# 1_PowerSupply.net
KiCad netlist of a schematic drawn in Altium Designer
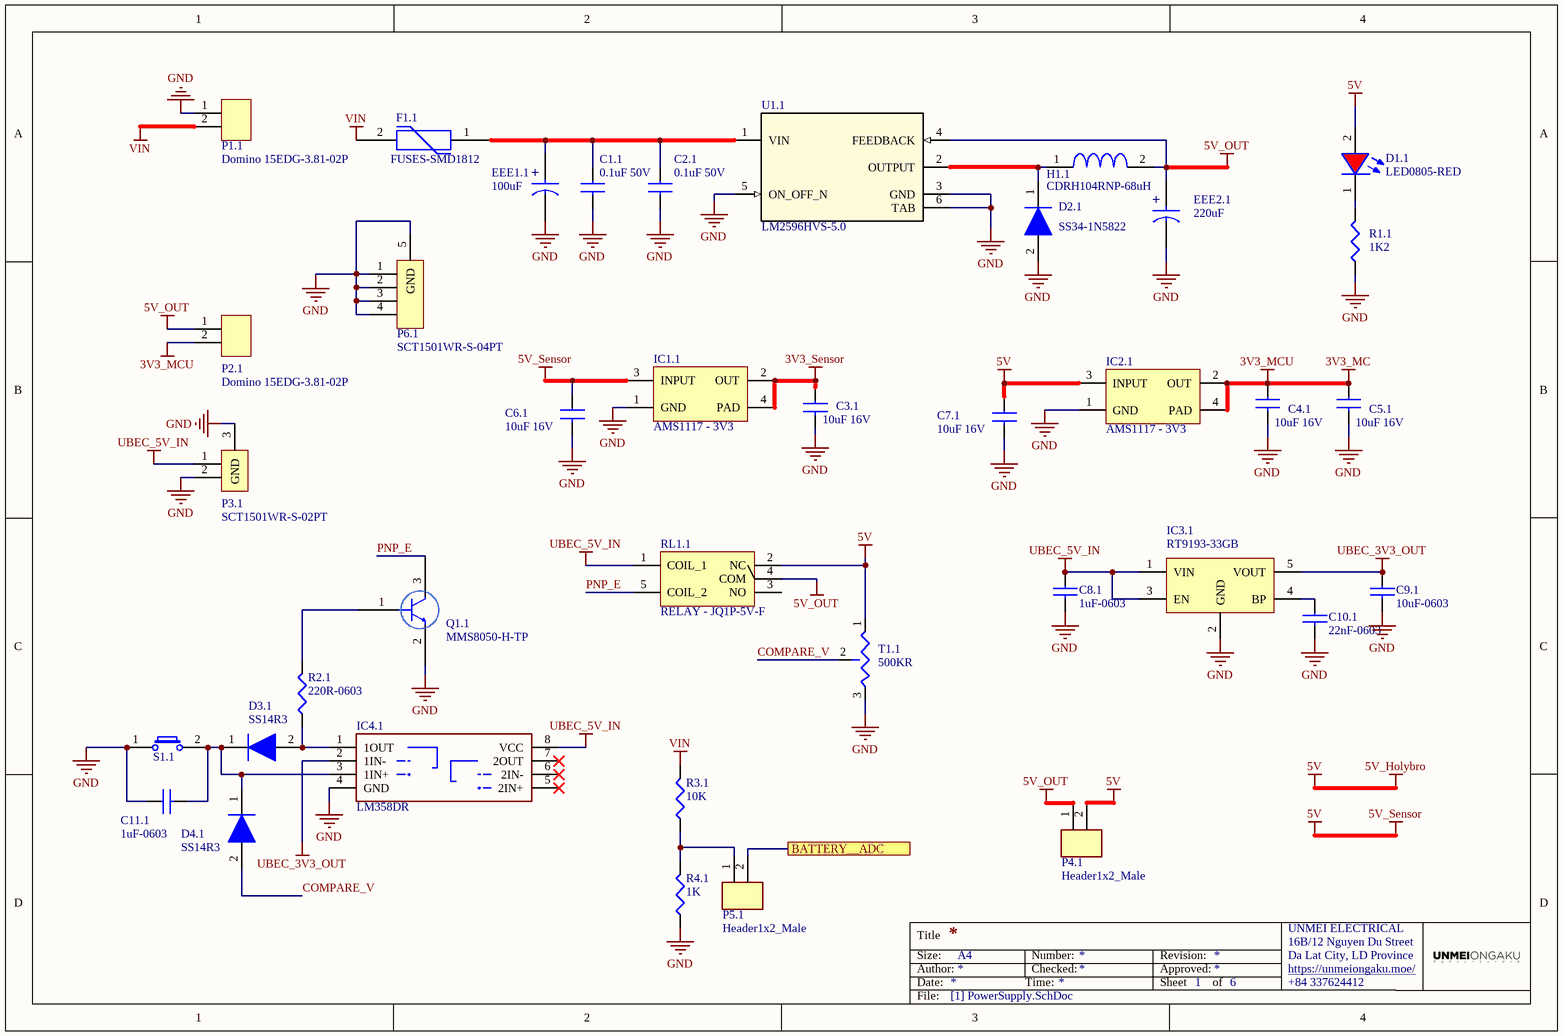
[diagram p0: [1] PowerSupply.SchDoc]

(export (version "E")
  (design (tool "Eeschema 10.0.6"))
  (components
    (comp (ref "C1.1")
      (value "0.1uF 50V")
      (footprint "CAP0805")
      (description "Cap Ceramic 0.1uF 50V X7R 10% SMD 2.0 x 1.2 mm 125 C Paper T/R")
      (fields
        (field (name "MANUFACTURER") "KEMET")
        (field (name "MANUFACTURER PART NUMBER") "C0805C104K5RACTU")
      )
      (libsource (lib "Minh_Lib") (part "C0805C104K5RACTU"))
    )
    (comp (ref "C2.1")
      (value "0.1uF 50V")
      (footprint "CAP0805")
      (description "Cap Ceramic 0.1uF 50V X7R 10% SMD 2.0 x 1.2 mm 125 C Paper T/R")
      (fields
        (field (name "MANUFACTURER") "KEMET")
        (field (name "MANUFACTURER PART NUMBER") "C0805C104K5RACTU")
      )
      (libsource (lib "Minh_Lib") (part "C0805C104K5RACTU"))
    )
    (comp (ref "C3.1")
      (value "10uF 16V")
      (footprint "CAP0805")
      (description "Ceramic Capacitors MLCC - SMD/SMT 16V 10uF X5R 0805 10%")
      (fields
        (field (name "MANUFACTURER") "KEMET")
        (field (name "MANUFACTURER PART NUMBER") "C0805C106K4PACTU")
      )
      (libsource (lib "Minh_Lib") (part "C0805C106K4PACTU"))
    )
    (comp (ref "C4.1")
      (value "10uF 16V")
      (footprint "CAP0805")
      (description "Ceramic Capacitors MLCC - SMD/SMT 16V 10uF X5R 0805 10%")
      (fields
        (field (name "MANUFACTURER") "KEMET")
        (field (name "MANUFACTURER PART NUMBER") "C0805C106K4PACTU")
      )
      (libsource (lib "Minh_Lib") (part "C0805C106K4PACTU"))
    )
    (comp (ref "C5.1")
      (value "10uF 16V")
      (footprint "CAP0805")
      (description "Ceramic Capacitors MLCC - SMD/SMT 16V 10uF X5R 0805 10%")
      (fields
        (field (name "MANUFACTURER") "KEMET")
        (field (name "MANUFACTURER PART NUMBER") "C0805C106K4PACTU")
      )
      (libsource (lib "Minh_Lib") (part "C0805C106K4PACTU"))
    )
    (comp (ref "C6.1")
      (value "10uF 16V")
      (footprint "CAP0805")
      (description "Ceramic Capacitors MLCC - SMD/SMT 16V 10uF X5R 0805 10%")
      (fields
        (field (name "MANUFACTURER") "KEMET")
        (field (name "MANUFACTURER PART NUMBER") "C0805C106K4PACTU")
      )
      (libsource (lib "Minh_Lib") (part "C0805C106K4PACTU"))
    )
    (comp (ref "C7.1")
      (value "10uF 16V")
      (footprint "CAP0805")
      (description "Ceramic Capacitors MLCC - SMD/SMT 16V 10uF X5R 0805 10%")
      (fields
        (field (name "MANUFACTURER") "KEMET")
        (field (name "MANUFACTURER PART NUMBER") "C0805C106K4PACTU")
      )
      (libsource (lib "Minh_Lib") (part "C0805C106K4PACTU"))
    )
    (comp (ref "C8.1")
      (value "1uF-0603")
      (footprint "CAP0603")
      (description "CAP CER 1UF 16V X7R 0603")
      (fields (field (name "TOLERANCE") "±10%"))
      (libsource (lib "Minh_Lib") (part "CC0603KRX7R7BB105"))
    )
    (comp (ref "C9.1")
      (value "10uF-0603")
      (footprint "CAP0603")
      (description "CAP CER 10UF 10V X5R 0603")
      (fields (field (name "TOLERANCE") "±10%"))
      (libsource (lib "Minh_Lib") (part "CC0603KRX5R6BB106"))
    )
    (comp (ref "C10.1")
      (value "22nF-0603")
      (footprint "CAP0603")
      (description "Multilayer Ceramic Capacitors MLCC - SMD/SMT 22nF 50V X7R 10%")
      (fields
        (field (name "MANUFACTURER") "Yageo")
        (field (name "MANUFACTURER PART NUMBER") "CC0603KRX7R9BB223")
      )
      (libsource (lib "Minh_Lib") (part "CC0603KRX7R9BB223"))
    )
    (comp (ref "C11.1")
      (value "1uF-0603")
      (footprint "CAP0603")
      (description "CAP CER 1UF 16V X7R 0603")
      (fields (field (name "TOLERANCE") "±10%"))
      (libsource (lib "Minh_Lib") (part "CC0603KRX7R7BB105"))
    )
    (comp (ref "D1.1")
      (value "LED0805-RED")
      (footprint "LED0805-RED")
      (libsource (lib "Minh_Lib") (part "LED0805-RED"))
    )
    (comp (ref "D2.1")
      (value "SS34-1N5822")
      (footprint "SS34 - 1N5822 / DO-214AA, SMA")
      (description "SS Series 500 mV 3 A 40 V Max Reverse Voltage Schottky Rectifier - DO-214AB")
      (fields
        (field (name "MANUFACTURER") "ON Semiconductor / Fairchild")
        (field (name "MANUFACTURER PART NUMBER") "SS34")
      )
      (libsource (lib "Minh_Lib") (part "SS34"))
    )
    (comp (ref "D3.1")
      (value "SS14R3")
      (footprint "SS14 - 1N5819 / DO-214AA, SMA")
      (description "1A, 40V, Schottky Rectifier")
      (fields (field (name "MANUFACTURER") "Taiwan Semiconductor"))
      (libsource (lib "Minh_Lib") (part "SS14R3"))
    )
    (comp (ref "D4.1")
      (value "SS14R3")
      (footprint "SS14 - 1N5819 / DO-214AA, SMA")
      (description "1A, 40V, Schottky Rectifier")
      (fields (field (name "MANUFACTURER") "Taiwan Semiconductor"))
      (libsource (lib "Minh_Lib") (part "SS14R3"))
    )
    (comp (ref "EEE1.1")
      (value "100uF")
      (footprint "CAPACITOR/ALU - SIZE D8/SMD - 6.3X7.7")
      (description "Cap Aluminum 100uF 25V 20% (6.3 X 7.7mm) SMD 143mA 2000h 85°C T/R")
      (fields
        (field (name "MANUFACTURER") "Panasonic")
        (field (name "MANUFACTURER PART NUMBER") "EEE-1EA101XP")
      )
      (libsource (lib "Minh_Lib") (part "EEE-1EA101XP"))
    )
    (comp (ref "EEE2.1")
      (value "220uF")
      (footprint "CAPACITOR/ALU - SIZE D8/SMD - 6.3X7.7")
      (description "Cap Aluminum 100uF 25V 20% (6.3 X 7.7mm) SMD 143mA 2000h 85°C T/R")
      (fields
        (field (name "MANUFACTURER") "Panasonic")
        (field (name "MANUFACTURER PART NUMBER") "EEE-1EA101XP")
      )
      (libsource (lib "Minh_Lib") (part "EEE-1EA101XP"))
    )
    (comp (ref "F1.1")
      (value "FUSES-SMD1812")
      (footprint "FUSES - SMD1812")
      (libsource (lib "Minh_Lib") (part "FUSES-SMD1812"))
    )
    (comp (ref "H1.1")
      (value "CDRH104RNP-68uH")
      (footprint "CDRH104RNP")
      (description "Ind Power Shielded Wirewound 68uH 30% 100KHz Ferrite 1.42A Carrier T/R")
      (fields
        (field (name "MANUFACTURER") "Sumida")
        (field (name "MANUFACTURER PART NUMBER") "CDRH104RNP-680NC")
      )
      (libsource (lib "Minh_Lib") (part "CDRH104RNP-680NC"))
    )
    (comp (ref "IC1.1")
      (value "AMS1117 - 3V3")
      (footprint "SOT223-4M_AMS1117_3V3")
      (description "LDO Voltage Regulators 3.3V 1A Positive")
      (fields
        (field (name "MANUFACTURER") "ON Semiconductor")
        (field (name "MANUFACTURER PART NUMBER") "NCP1117ST33T3G")
      )
      (libsource (lib "Minh_Lib") (part "AMS1117 - 3V3"))
    )
    (comp (ref "IC2.1")
      (value "AMS1117 - 3V3")
      (footprint "SOT223-4M_AMS1117_3V3")
      (description "LDO Voltage Regulators 3.3V 1A Positive")
      (fields
        (field (name "MANUFACTURER") "ON Semiconductor")
        (field (name "MANUFACTURER PART NUMBER") "NCP1117ST33T3G")
      )
      (libsource (lib "Minh_Lib") (part "AMS1117 - 3V3"))
    )
    (comp (ref "IC3.1")
      (value "RT9193-33GB")
      (footprint "SOT23-5")
      (description "IC REG LDO 3.3V 0.3A SOT23-5")
      (libsource (lib "Minh_Lib") (part "RT9193-33GB"))
    )
    (comp (ref "IC4.1")
      (value "LM358DR")
      (footprint "SOP8")
      (description "IC OPAMP GP 700KHZ 8SOIC")
      (fields (field (name "MANUFACTURER") "Texas Instruments"))
      (libsource (lib "Minh_Lib") (part "LM358DR"))
    )
    (comp (ref "P1.1")
      (value "Domino 15EDG-3.81-02P")
      (footprint "Domino 15EDG3.81 2P")
      (libsource (lib "Minh_Lib") (part "Domino 15EDG-3.81-02P"))
    )
    (comp (ref "P2.1")
      (value "Domino 15EDG-3.81-02P")
      (footprint "Domino 15EDG3.81 2P")
      (libsource (lib "Minh_Lib") (part "Domino 15EDG-3.81-02P"))
    )
    (comp (ref "P3.1")
      (value "SCT1501WR-S-02PT")
      (footprint "Connector ZH1.5 2P SMD")
      (libsource (lib "Minh_Lib") (part "SCT1501WR-S-02PT"))
    )
    (comp (ref "P4.1")
      (value "Header1x2_Male")
      (footprint "Minh_Lib:HDR1x2_2.54_MALE")
      (description "Header1x2_2.54_MALE")
      (libsource (lib "Minh_Lib") (part "HDR1x2_2.54_MALE"))
    )
    (comp (ref "P5.1")
      (value "Header1x2_Male")
      (footprint "Minh_Lib:HDR1x2_2.54_MALE")
      (description "Header1x2_2.54_MALE")
      (libsource (lib "Minh_Lib") (part "HDR1x2_2.54_MALE"))
    )
    (comp (ref "P6.1")
      (value "SCT1501WR-S-04PT")
      (footprint "Connector ZH1.5 4P SMD")
      (libsource (lib "Minh_Lib") (part "SCT1501WR-S-04PT"))
    )
    (comp (ref "Q1.1")
      (value "MMS8050-H-TP")
      (footprint "SOT23")
      (description "Trans Gp Bjt NPN 25V 0.5A 3-PIN SOT-23 T/r")
      (fields (field (name "MANUFACTURER") "MCC"))
      (libsource (lib "Minh_Lib") (part "MMS8050-H-TP"))
    )
    (comp (ref "R1.1")
      (value "1K2")
      (footprint "RES0805")
      (description "贴片电阻 1.5KΩ ±5% 1/8W ±100ppm/℃ 0805")
      (fields
        (field (name "MANUFACTURER") "Yageo")
        (field (name "MANUFACTURER PART NUMBER") "RC0805JR-071K5L")
      )
      (libsource (lib "Minh_Lib") (part "RC0805JR-071K5L"))
    )
    (comp (ref "R2.1")
      (value "220R-0603")
      (footprint "RES0603 - 3D")
      (description "RES SMD 220 OHM 5% 1/10W 0603")
      (fields (field (name "TOLERANCE") "±5%"))
      (libsource (lib "Minh_Lib") (part "RC0603JR-07220RL"))
    )
    (comp (ref "R3.1")
      (value "10K")
      (footprint "RES0805")
      (description "贴片电阻 10KΩ ±5% 1/8W ±100ppm/℃ 0805")
      (fields
        (field (name "MANUFACTURER") "Yageo")
        (field (name "MANUFACTURER PART NUMBER") "RC0805JR-0710KL")
      )
      (libsource (lib "Minh_Lib") (part "RC0805JR-0710KL"))
    )
    (comp (ref "R4.1")
      (value "1K")
      (footprint "RES0805")
      (description "贴片电阻 1KΩ ±5% 1/8W ±100ppm/℃ 0805")
      (fields
        (field (name "MANUFACTURER") "Yageo")
        (field (name "MANUFACTURER PART NUMBER") "RC0805JR-071KL")
      )
      (libsource (lib "Minh_Lib") (part "RC0805JR-071KL"))
    )
    (comp (ref "RL1.1")
      (value "RELAY - JQ1P-5V-F")
      (footprint "RELAY - JQ1P - XV - F 10A SPDT")
      (description "RELAY GEN PURPOSE SPDT 10A 5V")
      (fields (field (name "MANUFACTURER") "Panasonic") (field (name "MANUFACTURER PART NUMBER") "JQ1P-5V-F"))
      (libsource (lib "Minh_Lib") (part "RELAY - JQ1P-5V-F"))
    )
    (comp (ref "S1.1")
      (value "434121043816")
      (footprint "Switches-6x3.5x4.3mm")
      (description "Switch Tactile Spst-no 0.05A 12V")
      (fields (field (name "MANUFACTURER") "Wurth Electronics"))
      (libsource (lib "Minh_Lib") (part "434121043816"))
    )
    (comp (ref "T1.1")
      (value "500KR")
      (footprint "Rheostat - 3296W")
      (fields
        (field (name "MANUFACTURER") "Bourns")
        (field (name "MANUFACTURER PART NUMBER") "3296W-1-504LF")
        (field (name "TOLERANCE") "10%")
      )
      (libsource (lib "Minh_Lib") (part "3296W-1-504LF"))
    )
    (comp (ref "U1.1")
      (value "LM2596HVS-5.0")
      (footprint "Minh_Lib:TO265-5")
      (description "Optoisolator 5KV Trans 4SMD / Optocoupler Dc-in 1-CH Transistor Dc-out 4-PIN PDIP SMD")
      (fields
        (field (name "MANUFACTURER_PART_NUMBER") "LM2596S-ADJ/NOPB")
        (field (name "PARTNUMBER") "LM2596SX-ADJ/NOPB")
        (field (name "COPYRIGHT") "Copyright (C) 2021 Ultra Librarian. All rights reserved.")
      )
      (libsource (lib "Minh_Lib") (part "LM2596S-ADJ/NOPB"))
    )
  )
  (nets
    (net (code "1") (name "/BATTERY__ADC") (class "Default")
      (node (ref "P5.1") (pin "2") (pinfunction "2_2") (pintype "passive"))
    )
    (net (code "2") (name "/COMPARE_V") (class "Default")
      (node (ref "D4.1") (pin "2") (pintype "passive"))
      (node (ref "T1.1") (pin "2") (pinfunction "2_2") (pintype "passive"))
    )
    (net (code "3") (name "/PNP_E") (class "Default")
      (node (ref "Q1.1") (pin "3") (pinfunction "3_3") (pintype "passive"))
      (node (ref "RL1.1") (pin "5") (pinfunction "COIL_2_5") (pintype "passive"))
    )
    (net (code "4") (name "3V3_MC") (class "Default")
      (node (ref "C4.1") (pin "1") (pinfunction "1_1") (pintype "passive"))
      (node (ref "C5.1") (pin "1") (pinfunction "1_1") (pintype "passive"))
      (node (ref "IC2.1") (pin "2") (pinfunction "OUT_2") (pintype "passive"))
      (node (ref "IC2.1") (pin "4") (pinfunction "PAD_4") (pintype "passive"))
      (node (ref "P2.1") (pin "2") (pinfunction "2_2") (pintype "passive"))
    )
    (net (code "5") (name "3V3_Sensor") (class "Default")
      (node (ref "C3.1") (pin "1") (pinfunction "1_1") (pintype "passive"))
      (node (ref "IC1.1") (pin "2") (pinfunction "OUT_2") (pintype "passive"))
      (node (ref "IC1.1") (pin "4") (pinfunction "PAD_4") (pintype "passive"))
    )
    (net (code "6") (name "5V") (class "Default")
      (node (ref "C6.1") (pin "1") (pinfunction "1_1") (pintype "passive"))
      (node (ref "C7.1") (pin "1") (pinfunction "1_1") (pintype "passive"))
      (node (ref "D1.1") (pin "2") (pinfunction "+_2") (pintype "passive"))
      (node (ref "IC1.1") (pin "3") (pinfunction "INPUT_3") (pintype "power_in"))
      (node (ref "IC2.1") (pin "3") (pinfunction "INPUT_3") (pintype "power_in"))
      (node (ref "P4.1") (pin "2") (pinfunction "2_2") (pintype "passive"))
      (node (ref "RL1.1") (pin "2") (pinfunction "NC_2") (pintype "passive"))
      (node (ref "T1.1") (pin "1") (pinfunction "1_1") (pintype "passive"))
    )
    (net (code "7") (name "5V_OUT") (class "Default")
      (node (ref "EEE2.1") (pin "1") (pinfunction "1_1") (pintype "passive"))
      (node (ref "H1.1") (pin "2") (pinfunction "2_2") (pintype "passive"))
      (node (ref "P2.1") (pin "1") (pinfunction "1_1") (pintype "passive"))
      (node (ref "P4.1") (pin "1") (pinfunction "1_1") (pintype "passive"))
      (node (ref "RL1.1") (pin "4") (pinfunction "COM_4") (pintype "passive"))
      (node (ref "U1.1") (pin "4") (pinfunction "FEEDBACK_4") (pintype "input"))
    )
    (net (code "8") (name "GND") (class "Default")
      (node (ref "C1.1") (pin "2") (pinfunction "2_2") (pintype "passive"))
      (node (ref "C10.1") (pin "2") (pinfunction "2_2") (pintype "passive"))
      (node (ref "C11.1") (pin "1") (pinfunction "1_1") (pintype "passive"))
      (node (ref "C2.1") (pin "2") (pinfunction "2_2") (pintype "passive"))
      (node (ref "C3.1") (pin "2") (pinfunction "2_2") (pintype "passive"))
      (node (ref "C4.1") (pin "2") (pinfunction "2_2") (pintype "passive"))
      (node (ref "C5.1") (pin "2") (pinfunction "2_2") (pintype "passive"))
      (node (ref "C6.1") (pin "2") (pinfunction "2_2") (pintype "passive"))
      (node (ref "C7.1") (pin "2") (pinfunction "2_2") (pintype "passive"))
      (node (ref "C8.1") (pin "2") (pinfunction "2_2") (pintype "passive"))
      (node (ref "C9.1") (pin "2") (pinfunction "2_2") (pintype "passive"))
      (node (ref "D2.1") (pin "2") (pintype "passive"))
      (node (ref "EEE1.1") (pin "2") (pinfunction "2_2") (pintype "passive"))
      (node (ref "EEE2.1") (pin "2") (pinfunction "2_2") (pintype "passive"))
      (node (ref "IC1.1") (pin "1") (pinfunction "GND_1") (pintype "power_in"))
      (node (ref "IC2.1") (pin "1") (pinfunction "GND_1") (pintype "power_in"))
      (node (ref "IC3.1") (pin "2") (pinfunction "GND_2") (pintype "passive"))
      (node (ref "IC4.1") (pin "4") (pinfunction "GND_4") (pintype "passive"))
      (node (ref "P1.1") (pin "1") (pinfunction "1_1") (pintype "passive"))
      (node (ref "P3.1") (pin "2") (pinfunction "2_2") (pintype "passive"))
      (node (ref "P3.1") (pin "3") (pinfunction "GND_3") (pintype "passive"))
      (node (ref "P6.1") (pin "1") (pinfunction "1_1") (pintype "passive"))
      (node (ref "P6.1") (pin "2") (pinfunction "2_2") (pintype "passive"))
      (node (ref "P6.1") (pin "3") (pinfunction "3_3") (pintype "passive"))
      (node (ref "P6.1") (pin "4") (pinfunction "4_4") (pintype "passive"))
      (node (ref "P6.1") (pin "5") (pinfunction "GND_5") (pintype "passive"))
      (node (ref "Q1.1") (pin "2") (pinfunction "2_2") (pintype "passive"))
      (node (ref "R1.1") (pin "1") (pinfunction "1_1") (pintype "passive"))
      (node (ref "R4.1") (pin "1") (pinfunction "1_1") (pintype "passive"))
      (node (ref "S1.1") (pin "1") (pinfunction "1_1") (pintype "passive"))
      (node (ref "T1.1") (pin "3") (pinfunction "3_3") (pintype "passive"))
      (node (ref "U1.1") (pin "3") (pinfunction "GND_3") (pintype "power_in"))
      (node (ref "U1.1") (pin "5") (pinfunction "ON_OFF_N_5") (pintype "input"))
      (node (ref "U1.1") (pin "6") (pinfunction "TAB_6") (pintype "power_in"))
    )
    (net (code "9") (name "Net-(D1.1-+-Pad1)") (class "Default")
      (node (ref "D1.1") (pin "1") (pinfunction "+_1") (pintype "passive"))
      (node (ref "R1.1") (pin "2") (pinfunction "2_2") (pintype "passive"))
    )
    (net (code "10") (name "Net-(F1.1-0)") (class "Default")
      (node (ref "C1.1") (pin "1") (pinfunction "1_1") (pintype "passive"))
      (node (ref "C2.1") (pin "1") (pinfunction "1_1") (pintype "passive"))
      (node (ref "EEE1.1") (pin "1") (pinfunction "1_1") (pintype "passive"))
      (node (ref "F1.1") (pin "1") (pinfunction "0_1") (pintype "passive"))
      (node (ref "U1.1") (pin "1") (pinfunction "VIN_1") (pintype "power_in"))
    )
    (net (code "11") (name "Net-(IC3.1-BP)") (class "Default")
      (node (ref "C10.1") (pin "1") (pinfunction "1_1") (pintype "passive"))
      (node (ref "IC3.1") (pin "4") (pinfunction "BP_4") (pintype "passive"))
    )
    (net (code "12") (name "Net-(IC4.1-1IN+)") (class "Default")
      (node (ref "C11.1") (pin "2") (pinfunction "2_2") (pintype "passive"))
      (node (ref "D3.1") (pin "1") (pintype "passive"))
      (node (ref "D4.1") (pin "1") (pintype "passive"))
      (node (ref "IC4.1") (pin "3") (pinfunction "1IN+_3") (pintype "passive"))
      (node (ref "S1.1") (pin "2") (pinfunction "2_2") (pintype "passive"))
    )
    (net (code "13") (name "Net-(IC4.1-1OUT)") (class "Default")
      (node (ref "D3.1") (pin "2") (pintype "passive"))
      (node (ref "IC4.1") (pin "1") (pinfunction "1OUT_1") (pintype "passive"))
      (node (ref "R2.1") (pin "1") (pinfunction "1_1") (pintype "passive"))
    )
    (net (code "14") (name "Net-(P5.1-Pad1)") (class "Default")
      (node (ref "P5.1") (pin "1") (pinfunction "1_1") (pintype "passive"))
      (node (ref "R3.1") (pin "1") (pinfunction "1_1") (pintype "passive"))
      (node (ref "R4.1") (pin "2") (pinfunction "2_2") (pintype "passive"))
    )
    (net (code "15") (name "Net-(Q1.1-Pad1)") (class "Default")
      (node (ref "Q1.1") (pin "1") (pinfunction "1_1") (pintype "passive"))
      (node (ref "R2.1") (pin "2") (pinfunction "2_2") (pintype "passive"))
    )
    (net (code "16") (name "Net-(U1.1-OUTPUT)") (class "Default")
      (node (ref "D2.1") (pin "1") (pintype "passive"))
      (node (ref "H1.1") (pin "1") (pinfunction "1_1") (pintype "passive"))
      (node (ref "U1.1") (pin "2") (pinfunction "OUTPUT_2") (pintype "power_in"))
    )
    (net (code "17") (name "UBEC_3V3_OUT") (class "Default")
      (node (ref "C9.1") (pin "1") (pinfunction "1_1") (pintype "passive"))
      (node (ref "IC3.1") (pin "5") (pinfunction "VOUT_5") (pintype "power_in"))
      (node (ref "IC4.1") (pin "2") (pinfunction "1IN-_2") (pintype "passive"))
    )
    (net (code "18") (name "UBEC_5V_IN") (class "Default")
      (node (ref "C8.1") (pin "1") (pinfunction "1_1") (pintype "passive"))
      (node (ref "IC3.1") (pin "1") (pinfunction "VIN_1") (pintype "power_in"))
      (node (ref "IC3.1") (pin "3") (pinfunction "EN_3") (pintype "passive"))
      (node (ref "IC4.1") (pin "8") (pinfunction "VCC_8") (pintype "passive"))
      (node (ref "P3.1") (pin "1") (pinfunction "1_1") (pintype "passive"))
      (node (ref "RL1.1") (pin "1") (pinfunction "COIL_1_1") (pintype "passive"))
    )
    (net (code "19") (name "VIN") (class "Default")
      (node (ref "F1.1") (pin "2") (pinfunction "1_2") (pintype "passive"))
      (node (ref "P1.1") (pin "2") (pinfunction "2_2") (pintype "passive"))
      (node (ref "R3.1") (pin "2") (pinfunction "2_2") (pintype "passive"))
    )
    (net (code "20") (name "unconnected-(IC4.1-2IN+-Pad5)") (class "Default")
      (node (ref "IC4.1") (pin "5") (pinfunction "2IN+_5") (pintype "passive+no_connect"))
    )
    (net (code "21") (name "unconnected-(IC4.1-2IN--Pad6)") (class "Default")
      (node (ref "IC4.1") (pin "6") (pinfunction "2IN-_6") (pintype "passive+no_connect"))
    )
    (net (code "22") (name "unconnected-(IC4.1-2OUT-Pad7)") (class "Default")
      (node (ref "IC4.1") (pin "7") (pinfunction "2OUT_7") (pintype "passive+no_connect"))
    )
    (net (code "23") (name "unconnected-(RL1.1-NO-Pad3)") (class "Default")
      (node (ref "RL1.1") (pin "3") (pinfunction "NO_3") (pintype "passive"))
    )
  )
)
